# FPGA_Supply_Config.net
KiCad netlist of a schematic drawn in Altium Designer
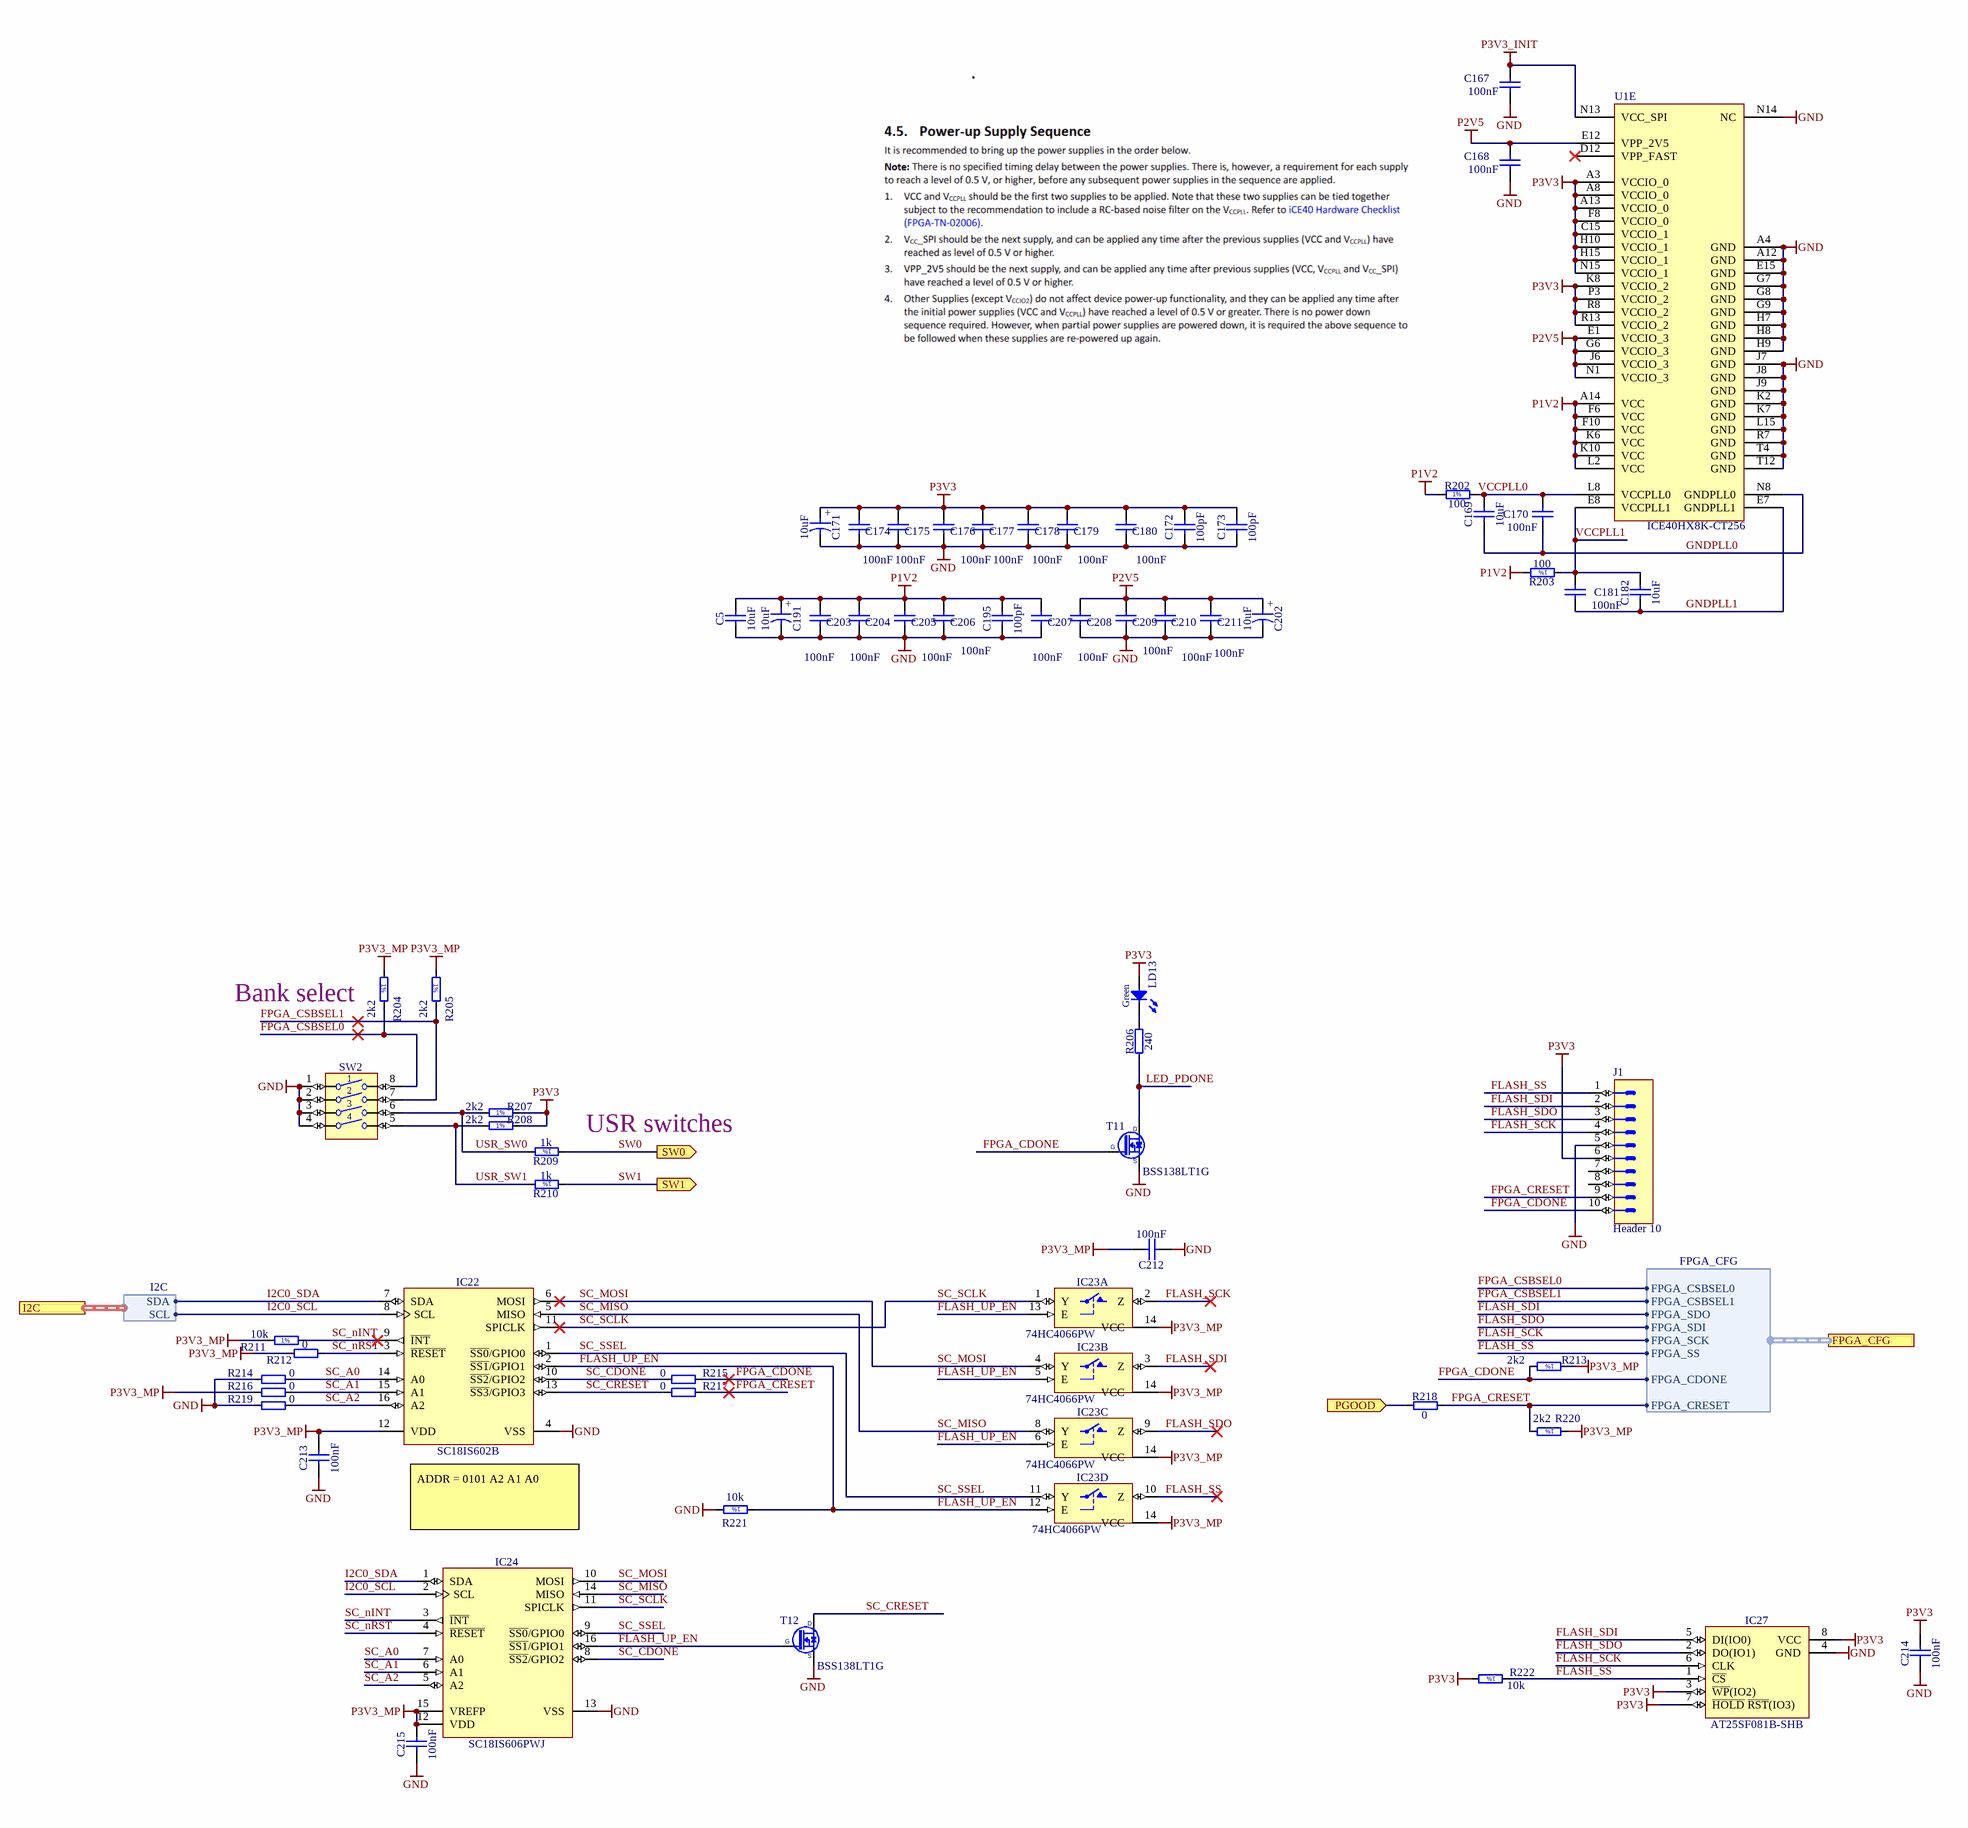
[diagram p0: FPGA_Supply_Config.SchDoc]

(export (version "E")
  (design (tool "Eeschema 10.0.6"))
  (components
    (comp (ref "C5")
      (value "10uF")
      (footprint "CAPC2012X135N")
      (description "Non-polarised capacitor")
      (fields
        (field (name "PART NUMBER") "CC0805_10UF_16V_10%_X5R")
        (field (name "VOLTAGE") "16V")
        (field (name "AUTHOR") "CERN DEM JLC")
      )
      (libsource (lib "Capacitors") (part "Capacitor - non polarized"))
    )
    (comp (ref "C167")
      (value "100nF")
      (footprint "CAPC1005X55N")
      (description "Non-polarised capacitor")
      (fields
        (field (name "PART NUMBER") "CC0402_100NF_16V_10%_X5R")
        (field (name "VOLTAGE") "16V")
        (field (name "AUTHOR") "CERN DEM JLC")
      )
      (libsource (lib "Capacitors") (part "Capacitor - non polarized"))
    )
    (comp (ref "C168")
      (value "100nF")
      (footprint "CAPC1005X55N")
      (description "Non-polarised capacitor")
      (fields
        (field (name "PART NUMBER") "CC0402_100NF_16V_10%_X5R")
        (field (name "VOLTAGE") "16V")
        (field (name "AUTHOR") "CERN DEM JLC")
      )
      (libsource (lib "Capacitors") (part "Capacitor - non polarized"))
    )
    (comp (ref "C169")
      (value "10uF")
      (footprint "CAPC1005X70N")
      (description "Non-polarised capacitor")
      (fields
        (field (name "PART NUMBER") "CC0402_10UF_6.3V_20%_X5R")
        (field (name "VOLTAGE") "6.3V")
        (field (name "AUTHOR") "CERN DEM JLC")
      )
      (libsource (lib "Capacitors") (part "Capacitor - non polarized"))
    )
    (comp (ref "C170")
      (value "100nF")
      (footprint "CAPC1005X55N")
      (description "Non-polarised capacitor")
      (fields
        (field (name "PART NUMBER") "CC0402_100NF_16V_10%_X5R")
        (field (name "VOLTAGE") "16V")
        (field (name "AUTHOR") "CERN DEM JLC")
      )
      (libsource (lib "Capacitors") (part "Capacitor - non polarized"))
    )
    (comp (ref "C171")
      (value "10uF")
      (footprint "CAPMP3216X180N")
      (description "Polarised capacitor")
      (fields
        (field (name "PART NUMBER") "CTE3216-18_10UF_16V_20%_AVX_TCJ")
        (field (name "VOLTAGE") "16V")
        (field (name "AUTHOR") "CERN DEM JLC")
      )
      (libsource (lib "Capacitors") (part "Capacitor - polarized"))
    )
    (comp (ref "C172")
      (value "100pF")
      (footprint "CAPC1005X55N")
      (description "Non-polarised capacitor")
      (fields
        (field (name "PART NUMBER") "CC0402_100PF_50V_5%_C0G")
        (field (name "VOLTAGE") "50V")
        (field (name "AUTHOR") "CERN DEM JLC")
      )
      (libsource (lib "Capacitors") (part "Capacitor - non polarized"))
    )
    (comp (ref "C173")
      (value "100pF")
      (footprint "CAPC1005X55N")
      (description "Non-polarised capacitor")
      (fields
        (field (name "PART NUMBER") "CC0402_100PF_50V_5%_C0G")
        (field (name "VOLTAGE") "50V")
        (field (name "AUTHOR") "CERN DEM JLC")
      )
      (libsource (lib "Capacitors") (part "Capacitor - non polarized"))
    )
    (comp (ref "C174")
      (value "100nF")
      (footprint "CAPC1005X55N")
      (description "Non-polarised capacitor")
      (fields
        (field (name "PART NUMBER") "CC0402_100NF_16V_10%_X5R")
        (field (name "VOLTAGE") "16V")
        (field (name "AUTHOR") "CERN DEM JLC")
      )
      (libsource (lib "Capacitors") (part "Capacitor - non polarized"))
    )
    (comp (ref "C175")
      (value "100nF")
      (footprint "CAPC1005X55N")
      (description "Non-polarised capacitor")
      (fields
        (field (name "PART NUMBER") "CC0402_100NF_16V_10%_X5R")
        (field (name "VOLTAGE") "16V")
        (field (name "AUTHOR") "CERN DEM JLC")
      )
      (libsource (lib "Capacitors") (part "Capacitor - non polarized"))
    )
    (comp (ref "C176")
      (value "100nF")
      (footprint "CAPC1005X55N")
      (description "Non-polarised capacitor")
      (fields
        (field (name "PART NUMBER") "CC0402_100NF_16V_10%_X5R")
        (field (name "VOLTAGE") "16V")
        (field (name "AUTHOR") "CERN DEM JLC")
      )
      (libsource (lib "Capacitors") (part "Capacitor - non polarized"))
    )
    (comp (ref "C177")
      (value "100nF")
      (footprint "CAPC1005X55N")
      (description "Non-polarised capacitor")
      (fields
        (field (name "PART NUMBER") "CC0402_100NF_16V_10%_X5R")
        (field (name "VOLTAGE") "16V")
        (field (name "AUTHOR") "CERN DEM JLC")
      )
      (libsource (lib "Capacitors") (part "Capacitor - non polarized"))
    )
    (comp (ref "C178")
      (value "100nF")
      (footprint "CAPC1005X55N")
      (description "Non-polarised capacitor")
      (fields
        (field (name "PART NUMBER") "CC0402_100NF_16V_10%_X5R")
        (field (name "VOLTAGE") "16V")
        (field (name "AUTHOR") "CERN DEM JLC")
      )
      (libsource (lib "Capacitors") (part "Capacitor - non polarized"))
    )
    (comp (ref "C179")
      (value "100nF")
      (footprint "CAPC1005X55N")
      (description "Non-polarised capacitor")
      (fields
        (field (name "PART NUMBER") "CC0402_100NF_16V_10%_X5R")
        (field (name "VOLTAGE") "16V")
        (field (name "AUTHOR") "CERN DEM JLC")
      )
      (libsource (lib "Capacitors") (part "Capacitor - non polarized"))
    )
    (comp (ref "C180")
      (value "100nF")
      (footprint "CAPC1005X55N")
      (description "Non-polarised capacitor")
      (fields
        (field (name "PART NUMBER") "CC0402_100NF_16V_10%_X5R")
        (field (name "VOLTAGE") "16V")
        (field (name "AUTHOR") "CERN DEM JLC")
      )
      (libsource (lib "Capacitors") (part "Capacitor - non polarized"))
    )
    (comp (ref "C181")
      (value "100nF")
      (footprint "CAPC1005X55N")
      (description "Non-polarised capacitor")
      (fields
        (field (name "PART NUMBER") "CC0402_100NF_16V_10%_X5R")
        (field (name "VOLTAGE") "16V")
        (field (name "AUTHOR") "CERN DEM JLC")
      )
      (libsource (lib "Capacitors") (part "Capacitor - non polarized"))
    )
    (comp (ref "C182")
      (value "10uF")
      (footprint "CAPC1005X70N")
      (description "Non-polarised capacitor")
      (fields
        (field (name "PART NUMBER") "CC0402_10UF_6.3V_20%_X5R")
        (field (name "VOLTAGE") "6.3V")
        (field (name "AUTHOR") "CERN DEM JLC")
      )
      (libsource (lib "Capacitors") (part "Capacitor - non polarized"))
    )
    (comp (ref "C191")
      (value "10uF")
      (footprint "CAPMP3216X180N")
      (description "Polarised capacitor")
      (fields
        (field (name "PART NUMBER") "CTE3216-18_10UF_16V_20%_AVX_TCJ")
        (field (name "VOLTAGE") "16V")
        (field (name "AUTHOR") "CERN DEM JLC")
      )
      (libsource (lib "Capacitors") (part "Capacitor - polarized"))
    )
    (comp (ref "C195")
      (value "100pF")
      (footprint "CAPC1005X55N")
      (description "Non-polarised capacitor")
      (fields
        (field (name "PART NUMBER") "CC0402_100PF_50V_5%_C0G")
        (field (name "VOLTAGE") "50V")
        (field (name "AUTHOR") "CERN DEM JLC")
      )
      (libsource (lib "Capacitors") (part "Capacitor - non polarized"))
    )
    (comp (ref "C202")
      (value "10uF")
      (footprint "CAPMP3216X180N")
      (description "Polarised capacitor")
      (fields
        (field (name "PART NUMBER") "CTE3216-18_10UF_16V_20%_AVX_TCJ")
        (field (name "VOLTAGE") "16V")
        (field (name "AUTHOR") "CERN DEM JLC")
      )
      (libsource (lib "Capacitors") (part "Capacitor - polarized"))
    )
    (comp (ref "C203")
      (value "100nF")
      (footprint "CAPC1005X55N")
      (description "Non-polarised capacitor")
      (fields
        (field (name "PART NUMBER") "CC0402_100NF_16V_10%_X5R")
        (field (name "VOLTAGE") "16V")
        (field (name "AUTHOR") "CERN DEM JLC")
      )
      (libsource (lib "Capacitors") (part "Capacitor - non polarized"))
    )
    (comp (ref "C204")
      (value "100nF")
      (footprint "CAPC1005X55N")
      (description "Non-polarised capacitor")
      (fields
        (field (name "PART NUMBER") "CC0402_100NF_16V_10%_X5R")
        (field (name "VOLTAGE") "16V")
        (field (name "AUTHOR") "CERN DEM JLC")
      )
      (libsource (lib "Capacitors") (part "Capacitor - non polarized"))
    )
    (comp (ref "C205")
      (value "100nF")
      (footprint "CAPC1005X55N")
      (description "Non-polarised capacitor")
      (fields
        (field (name "PART NUMBER") "CC0402_100NF_16V_10%_X5R")
        (field (name "VOLTAGE") "16V")
        (field (name "AUTHOR") "CERN DEM JLC")
      )
      (libsource (lib "Capacitors") (part "Capacitor - non polarized"))
    )
    (comp (ref "C206")
      (value "100nF")
      (footprint "CAPC1005X55N")
      (description "Non-polarised capacitor")
      (fields
        (field (name "PART NUMBER") "CC0402_100NF_16V_10%_X5R")
        (field (name "VOLTAGE") "16V")
        (field (name "AUTHOR") "CERN DEM JLC")
      )
      (libsource (lib "Capacitors") (part "Capacitor - non polarized"))
    )
    (comp (ref "C207")
      (value "100nF")
      (footprint "CAPC1005X55N")
      (description "Non-polarised capacitor")
      (fields
        (field (name "PART NUMBER") "CC0402_100NF_16V_10%_X5R")
        (field (name "VOLTAGE") "16V")
        (field (name "AUTHOR") "CERN DEM JLC")
      )
      (libsource (lib "Capacitors") (part "Capacitor - non polarized"))
    )
    (comp (ref "C208")
      (value "100nF")
      (footprint "CAPC1005X55N")
      (description "Non-polarised capacitor")
      (fields
        (field (name "PART NUMBER") "CC0402_100NF_16V_10%_X5R")
        (field (name "VOLTAGE") "16V")
        (field (name "AUTHOR") "CERN DEM JLC")
      )
      (libsource (lib "Capacitors") (part "Capacitor - non polarized"))
    )
    (comp (ref "C209")
      (value "100nF")
      (footprint "CAPC1005X55N")
      (description "Non-polarised capacitor")
      (fields
        (field (name "PART NUMBER") "CC0402_100NF_16V_10%_X5R")
        (field (name "VOLTAGE") "16V")
        (field (name "AUTHOR") "CERN DEM JLC")
      )
      (libsource (lib "Capacitors") (part "Capacitor - non polarized"))
    )
    (comp (ref "C210")
      (value "100nF")
      (footprint "CAPC1005X55N")
      (description "Non-polarised capacitor")
      (fields
        (field (name "PART NUMBER") "CC0402_100NF_16V_10%_X5R")
        (field (name "VOLTAGE") "16V")
        (field (name "AUTHOR") "CERN DEM JLC")
      )
      (libsource (lib "Capacitors") (part "Capacitor - non polarized"))
    )
    (comp (ref "C211")
      (value "100nF")
      (footprint "CAPC1005X55N")
      (description "Non-polarised capacitor")
      (fields
        (field (name "PART NUMBER") "CC0402_100NF_16V_10%_X5R")
        (field (name "VOLTAGE") "16V")
        (field (name "AUTHOR") "CERN DEM JLC")
      )
      (libsource (lib "Capacitors") (part "Capacitor - non polarized"))
    )
    (comp (ref "C212")
      (value "100nF")
      (footprint "CAPC1005X55N")
      (description "Non-polarised capacitor")
      (fields
        (field (name "PART NUMBER") "CC0402_100NF_16V_10%_X5R")
        (field (name "VOLTAGE") "16V")
        (field (name "AUTHOR") "CERN DEM JLC")
      )
      (libsource (lib "Capacitors") (part "Capacitor - non polarized"))
    )
    (comp (ref "C213")
      (value "100nF")
      (footprint "CAPC1005X55N")
      (description "Non-polarised capacitor")
      (fields
        (field (name "PART NUMBER") "CC0402_100NF_16V_10%_X5R")
        (field (name "VOLTAGE") "16V")
        (field (name "AUTHOR") "CERN DEM JLC")
      )
      (libsource (lib "Capacitors") (part "Capacitor - non polarized"))
    )
    (comp (ref "C214")
      (value "100nF")
      (footprint "CAPC1005X55N")
      (description "Non-polarised capacitor")
      (fields
        (field (name "PART NUMBER") "CC0402_100NF_16V_10%_X5R")
        (field (name "VOLTAGE") "16V")
        (field (name "AUTHOR") "CERN DEM JLC")
      )
      (libsource (lib "Capacitors") (part "Capacitor - non polarized"))
    )
    (comp (ref "C215")
      (value "100nF")
      (footprint "CAPC1005X55N")
      (description "Non-polarised capacitor")
      (fields
        (field (name "PART NUMBER") "CC0402_100NF_16V_10%_X5R")
        (field (name "VOLTAGE") "16V")
        (field (name "AUTHOR") "CERN DEM JLC")
      )
      (libsource (lib "Capacitors") (part "Capacitor - non polarized"))
    )
    (comp (ref "IC22")
      (value "SC18IS602B")
      (footprint "SOP65P640X110-16N")
      (description "I2C-bus to SPI bridge")
      (fields (field (name "MANUFACTURER") "NXP SEMICONDUCTORS") (field (name "AUTHOR") "CERN DEM MR"))
      (libsource (lib "ICs And Semiconductors") (part "SC18IS602B"))
    )
    (comp (ref "IC23")
      (value "74HC4066PW")
      (footprint "SOP65P640X110-14N")
      (fields (field (name "MANUFACTURER") "NXP SEMICONDUCTORS") (field (name "AUTHOR") "CERN DEM JLC"))
      (libsource (lib "ICs And Semiconductors") (part "4066"))
    )
    (comp (ref "IC24")
      (value "SC18IS606PWJ")
      (footprint "SOP65P640X110-16N")
      (description "I2C-bus to SPI bridge")
      (fields (field (name "MANUFACTURER") "NXP SEMICONDUCTORS") (field (name "AUTHOR") "GK"))
      (libsource (lib "ICS-logic") (part "SC18IS606PWJ"))
    )
    (comp (ref "IC27")
      (value "AT25SF081B-SHB")
      (footprint "SOIC127P790X216-8N")
      (description "8M-bit Serial Flash Memory with uniform 4KB sectors and Dual/Quad SPI and QPI")
      (fields (field (name "MANUFACTURER") "Renesas") (field (name "AUTHOR") "GK"))
      (libsource (lib "ICS-logic") (part "MEM_AT25SF081B-SHB"))
    )
    (comp (ref "J1")
      (value "Header 10")
      (footprint "HARWIN_M20-9980546")
      (description "Connector 10 Male")
      (fields
        (field (name "PART NUMBER") "HARWIN_M20-9980546")
        (field (name "MANUFACTURER") "HARWIN")
        (field (name "AUTHOR") "CERN DEM MR")
      )
      (libsource (lib "Connectors") (part "Connector 10 Male"))
    )
    (comp (ref "LD13")
      (value "Green")
      (footprint "LED_AVAGO_HSME-C120")
      (description "LED Green 1C 2A")
      (fields
        (field (name "PART NUMBER") "LED_AVAGO_HSME-C120")
        (field (name "MANUFACTURER") "AVAGO TECHNOLOGIES")
        (field (name "AUTHOR") "CERN DEM JMW")
      )
      (libsource (lib "ICs And Semiconductors") (part "LED Green 1C 2A"))
    )
    (comp (ref "R202")
      (value "100")
      (footprint "RESC1005X40N")
      (description "Resistor - 1%")
      (fields
        (field (name "PART NUMBER") "R0402_100R_1%_0.0625W_100PPM")
        (field (name "POWER") "0.0625W")
        (field (name "AUTHOR") "CERN DEM JLC")
      )
      (libsource (lib "Resistors") (part "Resistor - 1%"))
    )
    (comp (ref "R203")
      (value "100")
      (footprint "RESC1005X40N")
      (description "Resistor - 1%")
      (fields
        (field (name "PART NUMBER") "R0402_100R_1%_0.0625W_100PPM")
        (field (name "POWER") "0.0625W")
        (field (name "AUTHOR") "CERN DEM JLC")
      )
      (libsource (lib "Resistors") (part "Resistor - 1%"))
    )
    (comp (ref "R204")
      (value "2k2")
      (footprint "RESC1005X40N")
      (description "Resistor - 1%")
      (fields
        (field (name "PART NUMBER") "R0402_2K2_1%_0.0625W_100PPM")
        (field (name "POWER") "0.0625W")
        (field (name "AUTHOR") "CERN DEM JLC")
      )
      (libsource (lib "Resistors") (part "Resistor - 1%"))
    )
    (comp (ref "R205")
      (value "2k2")
      (footprint "RESC1005X40N")
      (description "Resistor - 1%")
      (fields
        (field (name "PART NUMBER") "R0402_2K2_1%_0.0625W_100PPM")
        (field (name "POWER") "0.0625W")
        (field (name "AUTHOR") "CERN DEM JLC")
      )
      (libsource (lib "Resistors") (part "Resistor - 1%"))
    )
    (comp (ref "R206")
      (value "240")
      (footprint "RESC1005X40N")
      (description "Resistor - 1%")
      (fields
        (field (name "PART NUMBER") "R0402_240R_1%_0.0625W_100PPM")
        (field (name "POWER") "0.0625W")
        (field (name "AUTHOR") "CERN DEM JLC")
      )
      (libsource (lib "Resistors") (part "Resistor - 1%"))
    )
    (comp (ref "R207")
      (value "2k2")
      (footprint "RESC1005X40N")
      (description "Resistor - 1%")
      (fields
        (field (name "PART NUMBER") "R0402_2K2_1%_0.0625W_100PPM")
        (field (name "POWER") "0.0625W")
        (field (name "AUTHOR") "CERN DEM JLC")
      )
      (libsource (lib "Resistors") (part "Resistor - 1%"))
    )
    (comp (ref "R208")
      (value "2k2")
      (footprint "RESC1005X40N")
      (description "Resistor - 1%")
      (fields
        (field (name "PART NUMBER") "R0402_2K2_1%_0.0625W_100PPM")
        (field (name "POWER") "0.0625W")
        (field (name "AUTHOR") "CERN DEM JLC")
      )
      (libsource (lib "Resistors") (part "Resistor - 1%"))
    )
    (comp (ref "R209")
      (value "1k")
      (footprint "RESC1005X40N")
      (description "Resistor - 1%")
      (fields
        (field (name "PART NUMBER") "R0402_1K_1%_0.0625W_100PPM")
        (field (name "POWER") "0.0625W")
        (field (name "AUTHOR") "CERN DEM JLC")
      )
      (libsource (lib "Resistors") (part "Resistor - 1%"))
    )
    (comp (ref "R210")
      (value "1k")
      (footprint "RESC1005X40N")
      (description "Resistor - 1%")
      (fields
        (field (name "PART NUMBER") "R0402_1K_1%_0.0625W_100PPM")
        (field (name "POWER") "0.0625W")
        (field (name "AUTHOR") "CERN DEM JLC")
      )
      (libsource (lib "Resistors") (part "Resistor - 1%"))
    )
    (comp (ref "R211")
      (value "10k")
      (footprint "RESC1005X40N")
      (description "Resistor - 1%")
      (fields
        (field (name "PART NUMBER") "R0402_10K_1%_0.0625W_100PPM")
        (field (name "POWER") "0.0625W")
        (field (name "AUTHOR") "CERN DEM JLC")
      )
      (libsource (lib "Resistors") (part "Resistor - 1%"))
    )
    (comp (ref "R212")
      (value "0")
      (footprint "RESC1005X40N")
      (description "Resistor")
      (fields
        (field (name "PART NUMBER") "R0402_0R_JUMPER")
        (field (name "MANUFACTURER") "GENERIC")
        (field (name "AUTHOR") "CERN DEM JLC")
      )
      (libsource (lib "Resistors") (part "Resistor"))
    )
    (comp (ref "R213")
      (value "2k2")
      (footprint "RESC1005X40N")
      (description "Resistor - 1%")
      (fields
        (field (name "PART NUMBER") "R0402_2K2_1%_0.0625W_100PPM")
        (field (name "POWER") "0.0625W")
        (field (name "AUTHOR") "CERN DEM JLC")
      )
      (libsource (lib "Resistors") (part "Resistor - 1%"))
    )
    (comp (ref "R214")
      (value "0")
      (footprint "RESC1005X40N")
      (description "Resistor")
      (fields
        (field (name "PART NUMBER") "R0402_0R_JUMPER")
        (field (name "MANUFACTURER") "GENERIC")
        (field (name "AUTHOR") "CERN DEM JLC")
      )
      (libsource (lib "Resistors") (part "Resistor"))
    )
    (comp (ref "R215")
      (value "0")
      (footprint "RESC1005X40N")
      (description "Resistor")
      (fields
        (field (name "PART NUMBER") "R0402_0R_JUMPER")
        (field (name "MANUFACTURER") "GENERIC")
        (field (name "AUTHOR") "CERN DEM JLC")
      )
      (libsource (lib "Resistors") (part "Resistor"))
    )
    (comp (ref "R216")
      (value "0")
      (footprint "RESC1005X40N")
      (description "Resistor")
      (fields
        (field (name "PART NUMBER") "R0402_0R_JUMPER")
        (field (name "MANUFACTURER") "GENERIC")
        (field (name "AUTHOR") "CERN DEM JLC")
      )
      (libsource (lib "Resistors") (part "Resistor"))
    )
    (comp (ref "R217")
      (value "0")
      (footprint "RESC1005X40N")
      (description "Resistor")
      (fields
        (field (name "PART NUMBER") "R0402_0R_JUMPER")
        (field (name "MANUFACTURER") "GENERIC")
        (field (name "AUTHOR") "CERN DEM JLC")
      )
      (libsource (lib "Resistors") (part "Resistor"))
    )
    (comp (ref "R218")
      (value "0")
      (footprint "RESC1005X40N")
      (description "Resistor")
      (fields
        (field (name "PART NUMBER") "R0402_0R_JUMPER")
        (field (name "MANUFACTURER") "GENERIC")
        (field (name "AUTHOR") "CERN DEM JLC")
      )
      (libsource (lib "Resistors") (part "Resistor"))
    )
    (comp (ref "R219")
      (value "0")
      (footprint "RESC1005X40N")
      (description "Resistor")
      (fields
        (field (name "PART NUMBER") "R0402_0R_JUMPER")
        (field (name "MANUFACTURER") "GENERIC")
        (field (name "AUTHOR") "CERN DEM JLC")
      )
      (libsource (lib "Resistors") (part "Resistor"))
    )
    (comp (ref "R220")
      (value "2k2")
      (footprint "RESC1005X40N")
      (description "Resistor - 1%")
      (fields
        (field (name "PART NUMBER") "R0402_2K2_1%_0.0625W_100PPM")
        (field (name "POWER") "0.0625W")
        (field (name "AUTHOR") "CERN DEM JLC")
      )
      (libsource (lib "Resistors") (part "Resistor - 1%"))
    )
    (comp (ref "R221")
      (value "10k")
      (footprint "RESC1005X40N")
      (description "Resistor - 1%")
      (fields
        (field (name "PART NUMBER") "R0402_10K_1%_0.0625W_100PPM")
        (field (name "POWER") "0.0625W")
        (field (name "AUTHOR") "CERN DEM JLC")
      )
      (libsource (lib "Resistors") (part "Resistor - 1%"))
    )
    (comp (ref "R222")
      (value "10k")
      (footprint "RESC1005X40N")
      (description "Resistor - 1%")
      (fields
        (field (name "PART NUMBER") "R0402_10K_1%_0.0625W_100PPM")
        (field (name "POWER") "0.0625W")
        (field (name "AUTHOR") "CERN DEM JLC")
      )
      (libsource (lib "Resistors") (part "Resistor - 1%"))
    )
    (comp (ref "SW2")
      (value "Switch")
      (footprint "SW_TYCO_1571983-4")
      (description "4 Ways SPST DIP Switch")
      (fields
        (field (name "PART NUMBER") "SW_TYCO_1571983-4")
        (field (name "MANUFACTURER") "TYCO")
        (field (name "AUTHOR") "CERN DEM JLC")
      )
      (libsource (lib "Eletro-mechanical") (part "SW 4x SPST DIP Switch"))
    )
    (comp (ref "T11")
      (value "BSS138LT1G")
      (footprint "SOT95P240X110-3N")
      (description "N-CHANNEL MOSFET WITH DIODE")
      (fields (field (name "MANUFACTURER") "ON SEMICONDUCTOR") (field (name "AUTHOR") "CERN DEM JLC"))
      (libsource (lib "ICs And Semiconductors") (part "N-MOSFET-D 1G 2S 3D"))
    )
    (comp (ref "T12")
      (value "BSS138LT1G")
      (footprint "SOT95P240X110-3N")
      (description "N-CHANNEL MOSFET WITH DIODE")
      (fields (field (name "MANUFACTURER") "ON SEMICONDUCTOR") (field (name "AUTHOR") "CERN DEM JLC"))
      (libsource (lib "ICs And Semiconductors") (part "N-MOSFET-D 1G 2S 3D"))
    )
    (comp (ref "U1")
      (value "ICE40HX8K-CT256")
      (footprint "LATC-caBGA-256")
      (fields (field (name "MANUFACTURER") "Lattice Semiconductor"))
      (libsource (lib "Altium Content Vault") (part "LATC-HX8K-caBGA-256"))
    )
  )
  (nets
    (net (code "3") (name "/FLASH_SCK") (class "Default")
      (node (ref "IC23") (pin "2") (pinfunction "Z_2") (pintype "bidirectional"))
      (node (ref "IC27") (pin "6") (pinfunction "CLK_6") (pintype "input"))
      (node (ref "J1") (pin "4") (pinfunction "4_4") (pintype "bidirectional"))
    )
    (net (code "4") (name "/FLASH_SDI") (class "Default")
      (node (ref "IC23") (pin "3") (pinfunction "Z_3") (pintype "bidirectional"))
      (node (ref "IC27") (pin "5") (pinfunction "DI(IO0)_5") (pintype "bidirectional"))
      (node (ref "J1") (pin "2") (pinfunction "2_2") (pintype "bidirectional"))
    )
    (net (code "5") (name "/FLASH_SDO") (class "Default")
      (node (ref "IC23") (pin "9") (pinfunction "Z_9") (pintype "bidirectional"))
      (node (ref "IC27") (pin "2") (pinfunction "DO(IO1)_2") (pintype "bidirectional"))
      (node (ref "J1") (pin "3") (pinfunction "3_3") (pintype "bidirectional"))
    )
    (net (code "6") (name "/FLASH_SS") (class "Default")
      (node (ref "IC23") (pin "10") (pinfunction "Z_10") (pintype "bidirectional"))
      (node (ref "IC27") (pin "1") (pinfunction "~{CS}_1") (pintype "input"))
      (node (ref "J1") (pin "1") (pinfunction "1_1") (pintype "bidirectional"))
      (node (ref "R222") (pin "1") (pinfunction "1_1") (pintype "passive"))
    )
    (net (code "7") (name "/FLASH_UP_EN") (class "Default")
      (node (ref "IC22") (pin "2") (pinfunction "~{SS1}/GPIO1_2") (pintype "bidirectional"))
      (node (ref "IC23") (pin "12") (pinfunction "E_12") (pintype "input"))
      (node (ref "IC23") (pin "13") (pinfunction "E_13") (pintype "input"))
      (node (ref "IC23") (pin "5") (pinfunction "E_5") (pintype "input"))
      (node (ref "IC23") (pin "6") (pinfunction "E_6") (pintype "input"))
      (node (ref "IC24") (pin "16") (pinfunction "~{SS1}/GPIO1_16") (pintype "bidirectional"))
      (node (ref "R221") (pin "1") (pinfunction "1_1") (pintype "passive"))
      (node (ref "T12") (pin "1") (pinfunction "G_1") (pintype "passive"))
    )
    (net (code "8") (name "/FPGA_CDONE") (class "Default")
      (node (ref "J1") (pin "10") (pinfunction "10_10") (pintype "bidirectional"))
      (node (ref "R213") (pin "2") (pinfunction "2_2") (pintype "passive"))
      (node (ref "R215") (pin "1") (pinfunction "1_1") (pintype "passive"))
      (node (ref "T11") (pin "1") (pinfunction "G_1") (pintype "passive"))
    )
    (net (code "9") (name "/FPGA_CRESET") (class "Default")
      (node (ref "J1") (pin "9") (pinfunction "9_9") (pintype "bidirectional"))
      (node (ref "R217") (pin "1") (pinfunction "1_1") (pintype "passive"))
      (node (ref "R218") (pin "2") (pinfunction "2_2") (pintype "passive"))
      (node (ref "R220") (pin "2") (pinfunction "2_2") (pintype "passive"))
    )
    (net (code "10") (name "/FPGA_CSBSEL0") (class "Default")
      (node (ref "R204") (pin "2") (pinfunction "2_2") (pintype "passive"))
      (node (ref "SW2") (pin "8") (pinfunction "8_8") (pintype "bidirectional"))
    )
    (net (code "11") (name "/FPGA_CSBSEL1") (class "Default")
      (node (ref "R205") (pin "2") (pinfunction "2_2") (pintype "passive"))
      (node (ref "SW2") (pin "7") (pinfunction "7_7") (pintype "bidirectional"))
    )
    (net (code "12") (name "/GNDPLL0") (class "Default")
      (node (ref "C169") (pin "1") (pinfunction "1_1") (pintype "passive"))
      (node (ref "C170") (pin "1") (pinfunction "1_1") (pintype "passive"))
      (node (ref "U1") (pin "N8") (pinfunction "GNDPLL0_N8") (pintype "power_in"))
    )
    (net (code "13") (name "/GNDPLL1") (class "Default")
      (node (ref "C181") (pin "1") (pinfunction "1_1") (pintype "passive"))
      (node (ref "C182") (pin "1") (pinfunction "1_1") (pintype "passive"))
      (node (ref "U1") (pin "E7") (pinfunction "GNDPLL1_E7") (pintype "power_in"))
    )
    (net (code "14") (name "/I2C0_SCL") (class "Default")
      (node (ref "IC22") (pin "8") (pinfunction "SCL_8") (pintype "input"))
      (node (ref "IC24") (pin "2") (pinfunction "SCL_2") (pintype "input"))
    )
    (net (code "15") (name "/I2C0_SDA") (class "Default")
      (node (ref "IC22") (pin "7") (pinfunction "SDA_7") (pintype "bidirectional"))
      (node (ref "IC24") (pin "1") (pinfunction "SDA_1") (pintype "bidirectional"))
    )
    (net (code "16") (name "/LED_PDONE") (class "Default")
      (node (ref "R206") (pin "1") (pinfunction "1_1") (pintype "passive"))
      (node (ref "T11") (pin "3") (pinfunction "D_3") (pintype "passive"))
    )
    (net (code "17") (name "/PGOOD") (class "Default")
      (node (ref "R218") (pin "1") (pinfunction "1_1") (pintype "passive"))
    )
    (net (code "18") (name "/SC_A0") (class "Default")
      (node (ref "IC22") (pin "14") (pinfunction "A0_14") (pintype "input"))
      (node (ref "IC24") (pin "7") (pinfunction "A0_7") (pintype "input"))
      (node (ref "R214") (pin "1") (pinfunction "1_1") (pintype "passive"))
    )
    (net (code "19") (name "/SC_A1") (class "Default")
      (node (ref "IC22") (pin "15") (pinfunction "A1_15") (pintype "input"))
      (node (ref "IC24") (pin "6") (pinfunction "A1_6") (pintype "input"))
      (node (ref "R216") (pin "1") (pinfunction "1_1") (pintype "passive"))
    )
    (net (code "20") (name "/SC_A2") (class "Default")
      (node (ref "IC22") (pin "16") (pinfunction "A2_16") (pintype "bidirectional"))
      (node (ref "IC24") (pin "5") (pinfunction "A2_5") (pintype "bidirectional"))
      (node (ref "R219") (pin "1") (pinfunction "1_1") (pintype "passive"))
    )
    (net (code "21") (name "/SC_CDONE") (class "Default")
      (node (ref "IC22") (pin "10") (pinfunction "~{SS2}/GPIO2_10") (pintype "bidirectional"))
      (node (ref "IC24") (pin "8") (pinfunction "~{SS2}/GPIO2_8") (pintype "bidirectional"))
      (node (ref "R215") (pin "2") (pinfunction "2_2") (pintype "passive"))
    )
    (net (code "22") (name "/SC_CRESET") (class "Default")
      (node (ref "IC22") (pin "13") (pinfunction "~{SS3}/GPIO3_13") (pintype "bidirectional"))
      (node (ref "R217") (pin "2") (pinfunction "2_2") (pintype "passive"))
      (node (ref "T12") (pin "3") (pinfunction "D_3") (pintype "passive"))
    )
    (net (code "23") (name "/SC_MISO") (class "Default")
      (node (ref "IC22") (pin "5") (pinfunction "MISO_5") (pintype "input"))
      (node (ref "IC23") (pin "8") (pinfunction "Y_8") (pintype "bidirectional"))
      (node (ref "IC24") (pin "14") (pinfunction "MISO_14") (pintype "input"))
    )
    (net (code "24") (name "/SC_MOSI") (class "Default")
      (node (ref "IC22") (pin "6") (pinfunction "MOSI_6") (pintype "output"))
      (node (ref "IC23") (pin "4") (pinfunction "Y_4") (pintype "bidirectional"))
      (node (ref "IC24") (pin "10") (pinfunction "MOSI_10") (pintype "output"))
    )
    (net (code "25") (name "/SC_SCLK") (class "Default")
      (node (ref "IC22") (pin "11") (pinfunction "SPICLK_11") (pintype "output"))
      (node (ref "IC23") (pin "1") (pinfunction "Y_1") (pintype "bidirectional"))
      (node (ref "IC24") (pin "11") (pinfunction "SPICLK_11") (pintype "output"))
    )
    (net (code "26") (name "/SC_SSEL") (class "Default")
      (node (ref "IC22") (pin "1") (pinfunction "~{SS0}/GPIO0_1") (pintype "bidirectional"))
      (node (ref "IC23") (pin "11") (pinfunction "Y_11") (pintype "bidirectional"))
      (node (ref "IC24") (pin "9") (pinfunction "~{SS0}/GPIO0_9") (pintype "bidirectional"))
    )
    (net (code "27") (name "/SC_nINT") (class "Default")
      (node (ref "IC22") (pin "9") (pinfunction "~{INT}_9") (pintype "output"))
      (node (ref "IC24") (pin "3") (pinfunction "~{INT}_3") (pintype "output"))
      (node (ref "R211") (pin "2") (pinfunction "2_2") (pintype "passive"))
    )
    (net (code "28") (name "/SC_nRST") (class "Default")
      (node (ref "IC22") (pin "3") (pinfunction "~{RESET}_3") (pintype "input"))
      (node (ref "IC24") (pin "4") (pinfunction "~{RESET}_4") (pintype "input"))
      (node (ref "R212") (pin "1") (pinfunction "1_1") (pintype "passive"))
    )
    (net (code "29") (name "/SW0") (class "Default")
      (node (ref "R209") (pin "1") (pinfunction "1_1") (pintype "passive"))
    )
    (net (code "30") (name "/SW1") (class "Default")
      (node (ref "R210") (pin "1") (pinfunction "1_1") (pintype "passive"))
    )
    (net (code "31") (name "/USR_SW0") (class "Default")
      (node (ref "R207") (pin "1") (pinfunction "1_1") (pintype "passive"))
      (node (ref "R209") (pin "2") (pinfunction "2_2") (pintype "passive"))
      (node (ref "SW2") (pin "6") (pinfunction "6_6") (pintype "bidirectional"))
    )
    (net (code "32") (name "/USR_SW1") (class "Default")
      (node (ref "R208") (pin "1") (pinfunction "1_1") (pintype "passive"))
      (node (ref "R210") (pin "2") (pinfunction "2_2") (pintype "passive"))
      (node (ref "SW2") (pin "5") (pinfunction "5_5") (pintype "bidirectional"))
    )
    (net (code "33") (name "/VCCPLL0") (class "Default")
      (node (ref "C169") (pin "2") (pinfunction "2_2") (pintype "passive"))
      (node (ref "C170") (pin "2") (pinfunction "2_2") (pintype "passive"))
      (node (ref "R202") (pin "2") (pinfunction "2_2") (pintype "passive"))
      (node (ref "U1") (pin "L8") (pinfunction "VCCPLL0_L8") (pintype "power_in"))
    )
    (net (code "34") (name "/VCCPLL1") (class "Default")
      (node (ref "C181") (pin "2") (pinfunction "2_2") (pintype "passive"))
      (node (ref "C182") (pin "2") (pinfunction "2_2") (pintype "passive"))
      (node (ref "R203") (pin "1") (pinfunction "1_1") (pintype "passive"))
      (node (ref "U1") (pin "E8") (pinfunction "VCCPLL1_E8") (pintype "power_in"))
    )
    (net (code "37") (name "GND") (class "Default")
      (node (ref "C167") (pin "1") (pinfunction "1_1") (pintype "passive"))
      (node (ref "C168") (pin "1") (pinfunction "1_1") (pintype "passive"))
      (node (ref "C171") (pin "2") (pinfunction "2_2") (pintype "passive"))
      (node (ref "C172") (pin "1") (pinfunction "1_1") (pintype "passive"))
      (node (ref "C173") (pin "1") (pinfunction "1_1") (pintype "passive"))
      (node (ref "C174") (pin "1") (pinfunction "1_1") (pintype "passive"))
      (node (ref "C175") (pin "1") (pinfunction "1_1") (pintype "passive"))
      (node (ref "C176") (pin "1") (pinfunction "1_1") (pintype "passive"))
      (node (ref "C177") (pin "1") (pinfunction "1_1") (pintype "passive"))
      (node (ref "C178") (pin "1") (pinfunction "1_1") (pintype "passive"))
      (node (ref "C179") (pin "1") (pinfunction "1_1") (pintype "passive"))
      (node (ref "C180") (pin "1") (pinfunction "1_1") (pintype "passive"))
      (node (ref "C191") (pin "2") (pinfunction "2_2") (pintype "passive"))
      (node (ref "C195") (pin "1") (pinfunction "1_1") (pintype "passive"))
      (node (ref "C202") (pin "2") (pinfunction "2_2") (pintype "passive"))
      (node (ref "C203") (pin "1") (pinfunction "1_1") (pintype "passive"))
      (node (ref "C204") (pin "1") (pinfunction "1_1") (pintype "passive"))
      (node (ref "C205") (pin "1") (pinfunction "1_1") (pintype "passive"))
      (node (ref "C206") (pin "1") (pinfunction "1_1") (pintype "passive"))
      (node (ref "C207") (pin "1") (pinfunction "1_1") (pintype "passive"))
      (node (ref "C208") (pin "1") (pinfunction "1_1") (pintype "passive"))
      (node (ref "C209") (pin "1") (pinfunction "1_1") (pintype "passive"))
      (node (ref "C210") (pin "1") (pinfunction "1_1") (pintype "passive"))
      (node (ref "C211") (pin "1") (pinfunction "1_1") (pintype "passive"))
      (node (ref "C212") (pin "1") (pinfunction "1_1") (pintype "passive"))
      (node (ref "C213") (pin "1") (pinfunction "1_1") (pintype "passive"))
      (node (ref "C214") (pin "1") (pinfunction "1_1") (pintype "passive"))
      (node (ref "C215") (pin "1") (pinfunction "1_1") (pintype "passive"))
      (node (ref "C5") (pin "1") (pinfunction "1_1") (pintype "passive"))
      (node (ref "IC22") (pin "4") (pinfunction "VSS_4") (pintype "power_in"))
      (node (ref "IC23") (pin "7") (pinfunction "GND_7") (pintype "power_in"))
      (node (ref "IC24") (pin "13") (pinfunction "VSS_13") (pintype "power_in"))
      (node (ref "IC27") (pin "4") (pinfunction "GND_4") (pintype "power_in"))
      (node (ref "J1") (pin "5") (pinfunction "5_5") (pintype "bidirectional"))
      (node (ref "R214") (pin "2") (pinfunction "2_2") (pintype "passive"))
      (node (ref "R219") (pin "2") (pinfunction "2_2") (pintype "passive"))
      (node (ref "R221") (pin "2") (pinfunction "2_2") (pintype "passive"))
      (node (ref "SW2") (pin "1") (pinfunction "1_1") (pintype "bidirectional"))
      (node (ref "SW2") (pin "2") (pinfunction "2_2") (pintype "bidirectional"))
      (node (ref "SW2") (pin "3") (pinfunction "3_3") (pintype "bidirectional"))
      (node (ref "SW2") (pin "4") (pinfunction "4_4") (pintype "bidirectional"))
      (node (ref "T11") (pin "2") (pinfunction "S_2") (pintype "passive"))
      (node (ref "T12") (pin "2") (pinfunction "S_2") (pintype "passive"))
      (node (ref "U1") (pin "A12") (pinfunction "GND_A12") (pintype "power_in"))
      (node (ref "U1") (pin "A4") (pinfunction "GND_A4") (pintype "power_in"))
      (node (ref "U1") (pin "E15") (pinfunction "GND_E15") (pintype "power_in"))
      (node (ref "U1") (pin "G7") (pinfunction "GND_G7") (pintype "power_in"))
      (node (ref "U1") (pin "G8") (pinfunction "GND_G8") (pintype "power_in"))
      (node (ref "U1") (pin "G9") (pinfunction "GND_G9") (pintype "power_in"))
      (node (ref "U1") (pin "H7") (pinfunction "GND_H7") (pintype "power_in"))
      (node (ref "U1") (pin "H8") (pinfunction "GND_H8") (pintype "power_in"))
      (node (ref "U1") (pin "H9") (pinfunction "GND_H9") (pintype "power_in"))
      (node (ref "U1") (pin "J7") (pinfunction "GND_J7") (pintype "power_in"))
      (node (ref "U1") (pin "J8") (pinfunction "GND_J8") (pintype "power_in"))
      (node (ref "U1") (pin "J9") (pinfunction "GND_J9") (pintype "power_in"))
      (node (ref "U1") (pin "K2") (pinfunction "GND_K2") (pintype "power_in"))
      (node (ref "U1") (pin "K7") (pinfunction "GND_K7") (pintype "power_in"))
      (node (ref "U1") (pin "L15") (pinfunction "GND_L15") (pintype "power_in"))
      (node (ref "U1") (pin "N14") (pinfunction "NC_N14") (pintype "passive"))
      (node (ref "U1") (pin "R7") (pinfunction "GND_R7") (pintype "power_in"))
      (node (ref "U1") (pin "T12") (pinfunction "GND_T12") (pintype "power_in"))
      (node (ref "U1") (pin "T4") (pinfunction "GND_T4") (pintype "power_in"))
    )
    (net (code "38") (name "Net-(LD13-C)") (class "Default")
      (node (ref "LD13") (pin "1") (pinfunction "C_1") (pintype "passive"))
      (node (ref "R206") (pin "2") (pinfunction "2_2") (pintype "passive"))
    )
    (net (code "39") (name "P1V2") (class "Default")
      (node (ref "C191") (pin "1") (pinfunction "1_1") (pintype "passive"))
      (node (ref "C195") (pin "2") (pinfunction "2_2") (pintype "passive"))
      (node (ref "C203") (pin "2") (pinfunction "2_2") (pintype "passive"))
      (node (ref "C204") (pin "2") (pinfunction "2_2") (pintype "passive"))
      (node (ref "C205") (pin "2") (pinfunction "2_2") (pintype "passive"))
      (node (ref "C206") (pin "2") (pinfunction "2_2") (pintype "passive"))
      (node (ref "C207") (pin "2") (pinfunction "2_2") (pintype "passive"))
      (node (ref "C5") (pin "2") (pinfunction "2_2") (pintype "passive"))
      (node (ref "R202") (pin "1") (pinfunction "1_1") (pintype "passive"))
      (node (ref "R203") (pin "2") (pinfunction "2_2") (pintype "passive"))
      (node (ref "U1") (pin "A14") (pinfunction "VCC_A14") (pintype "power_in"))
      (node (ref "U1") (pin "F10") (pinfunction "VCC_F10") (pintype "power_in"))
      (node (ref "U1") (pin "F6") (pinfunction "VCC_F6") (pintype "power_in"))
      (node (ref "U1") (pin "K10") (pinfunction "VCC_K10") (pintype "power_in"))
      (node (ref "U1") (pin "K6") (pinfunction "VCC_K6") (pintype "power_in"))
      (node (ref "U1") (pin "L2") (pinfunction "VCC_L2") (pintype "power_in"))
    )
    (net (code "40") (name "P2V5") (class "Default")
      (node (ref "C168") (pin "2") (pinfunction "2_2") (pintype "passive"))
      (node (ref "C202") (pin "1") (pinfunction "1_1") (pintype "passive"))
      (node (ref "C208") (pin "2") (pinfunction "2_2") (pintype "passive"))
      (node (ref "C209") (pin "2") (pinfunction "2_2") (pintype "passive"))
      (node (ref "C210") (pin "2") (pinfunction "2_2") (pintype "passive"))
      (node (ref "C211") (pin "2") (pinfunction "2_2") (pintype "passive"))
      (node (ref "U1") (pin "E1") (pinfunction "VCCIO_3_E1") (pintype "power_in"))
      (node (ref "U1") (pin "E12") (pinfunction "VPP_2V5_E12") (pintype "power_in"))
      (node (ref "U1") (pin "G6") (pinfunction "VCCIO_3_G6") (pintype "power_in"))
      (node (ref "U1") (pin "J6") (pinfunction "VCCIO_3_J6") (pintype "power_in"))
      (node (ref "U1") (pin "N1") (pinfunction "VCCIO_3_N1") (pintype "power_in"))
    )
    (net (code "41") (name "P3V3") (class "Default")
      (node (ref "C171") (pin "1") (pinfunction "1_1") (pintype "passive"))
      (node (ref "C172") (pin "2") (pinfunction "2_2") (pintype "passive"))
      (node (ref "C173") (pin "2") (pinfunction "2_2") (pintype "passive"))
      (node (ref "C174") (pin "2") (pinfunction "2_2") (pintype "passive"))
      (node (ref "C175") (pin "2") (pinfunction "2_2") (pintype "passive"))
      (node (ref "C176") (pin "2") (pinfunction "2_2") (pintype "passive"))
      (node (ref "C177") (pin "2") (pinfunction "2_2") (pintype "passive"))
      (node (ref "C178") (pin "2") (pinfunction "2_2") (pintype "passive"))
      (node (ref "C179") (pin "2") (pinfunction "2_2") (pintype "passive"))
      (node (ref "C180") (pin "2") (pinfunction "2_2") (pintype "passive"))
      (node (ref "C214") (pin "2") (pinfunction "2_2") (pintype "passive"))
      (node (ref "IC27") (pin "3") (pinfunction "~{WP}(IO2)_3") (pintype "bidirectional"))
      (node (ref "IC27") (pin "7") (pinfunction "~{HOLD}_~{RST}(IO3)_7") (pintype "bidirectional"))
      (node (ref "IC27") (pin "8") (pinfunction "VCC_8") (pintype "power_in"))
      (node (ref "J1") (pin "6") (pinfunction "6_6") (pintype "bidirectional"))
      (node (ref "LD13") (pin "2") (pinfunction "A_2") (pintype "passive"))
      (node (ref "R207") (pin "2") (pinfunction "2_2") (pintype "passive"))
      (node (ref "R208") (pin "2") (pinfunction "2_2") (pintype "passive"))
      (node (ref "R222") (pin "2") (pinfunction "2_2") (pintype "passive"))
      (node (ref "U1") (pin "A13") (pinfunction "VCCIO_0_A13") (pintype "power_in"))
      (node (ref "U1") (pin "A3") (pinfunction "VCCIO_0_A3") (pintype "power_in"))
      (node (ref "U1") (pin "A8") (pinfunction "VCCIO_0_A8") (pintype "power_in"))
      (node (ref "U1") (pin "C15") (pinfunction "VCCIO_1_C15") (pintype "power_in"))
      (node (ref "U1") (pin "F8") (pinfunction "VCCIO_0_F8") (pintype "power_in"))
      (node (ref "U1") (pin "H10") (pinfunction "VCCIO_1_H10") (pintype "power_in"))
      (node (ref "U1") (pin "H15") (pinfunction "VCCIO_1_H15") (pintype "power_in"))
      (node (ref "U1") (pin "K8") (pinfunction "VCCIO_2_K8") (pintype "power_in"))
      (node (ref "U1") (pin "N15") (pinfunction "VCCIO_1_N15") (pintype "power_in"))
      (node (ref "U1") (pin "P3") (pinfunction "VCCIO_2_P3") (pintype "power_in"))
      (node (ref "U1") (pin "R13") (pinfunction "VCCIO_2_R13") (pintype "power_in"))
      (node (ref "U1") (pin "R8") (pinfunction "VCCIO_2_R8") (pintype "power_in"))
    )
    (net (code "42") (name "P3V3_INIT") (class "Default")
      (node (ref "C167") (pin "2") (pinfunction "2_2") (pintype "passive"))
      (node (ref "U1") (pin "N13") (pinfunction "VCC_SPI_N13") (pintype "power_in"))
    )
    (net (code "43") (name "P3V3_MP") (class "Default")
      (node (ref "C212") (pin "2") (pinfunction "2_2") (pintype "passive"))
      (node (ref "C213") (pin "2") (pinfunction "2_2") (pintype "passive"))
      (node (ref "C215") (pin "2") (pinfunction "2_2") (pintype "passive"))
      (node (ref "IC22") (pin "12") (pinfunction "VDD_12") (pintype "power_in"))
      (node (ref "IC23") (pin "14") (pinfunction "VCC_14") (pintype "power_in"))
      (node (ref "IC24") (pin "12") (pinfunction "VDD_12") (pintype "power_in"))
      (node (ref "IC24") (pin "15") (pinfunction "VREFP_15") (pintype "power_in"))
      (node (ref "R204") (pin "1") (pinfunction "1_1") (pintype "passive"))
      (node (ref "R205") (pin "1") (pinfunction "1_1") (pintype "passive"))
      (node (ref "R211") (pin "1") (pinfunction "1_1") (pintype "passive"))
      (node (ref "R212") (pin "2") (pinfunction "2_2") (pintype "passive"))
      (node (ref "R213") (pin "1") (pinfunction "1_1") (pintype "passive"))
      (node (ref "R216") (pin "2") (pinfunction "2_2") (pintype "passive"))
      (node (ref "R220") (pin "1") (pinfunction "1_1") (pintype "passive"))
    )
    (net (code "44") (name "unconnected-(J1-Pad7)") (class "Default")
      (node (ref "J1") (pin "7") (pinfunction "7_7") (pintype "bidirectional"))
    )
    (net (code "45") (name "unconnected-(J1-Pad8)") (class "Default")
      (node (ref "J1") (pin "8") (pinfunction "8_8") (pintype "bidirectional"))
    )
    (net (code "46") (name "unconnected-(U1E-VPP_FAST-PadD12)") (class "Default")
      (node (ref "U1") (pin "D12") (pinfunction "VPP_FAST_D12") (pintype "power_in+no_connect"))
    )
  )
)
